# 503DC24.net
KiCad netlist of a schematic drawn in EAGLE
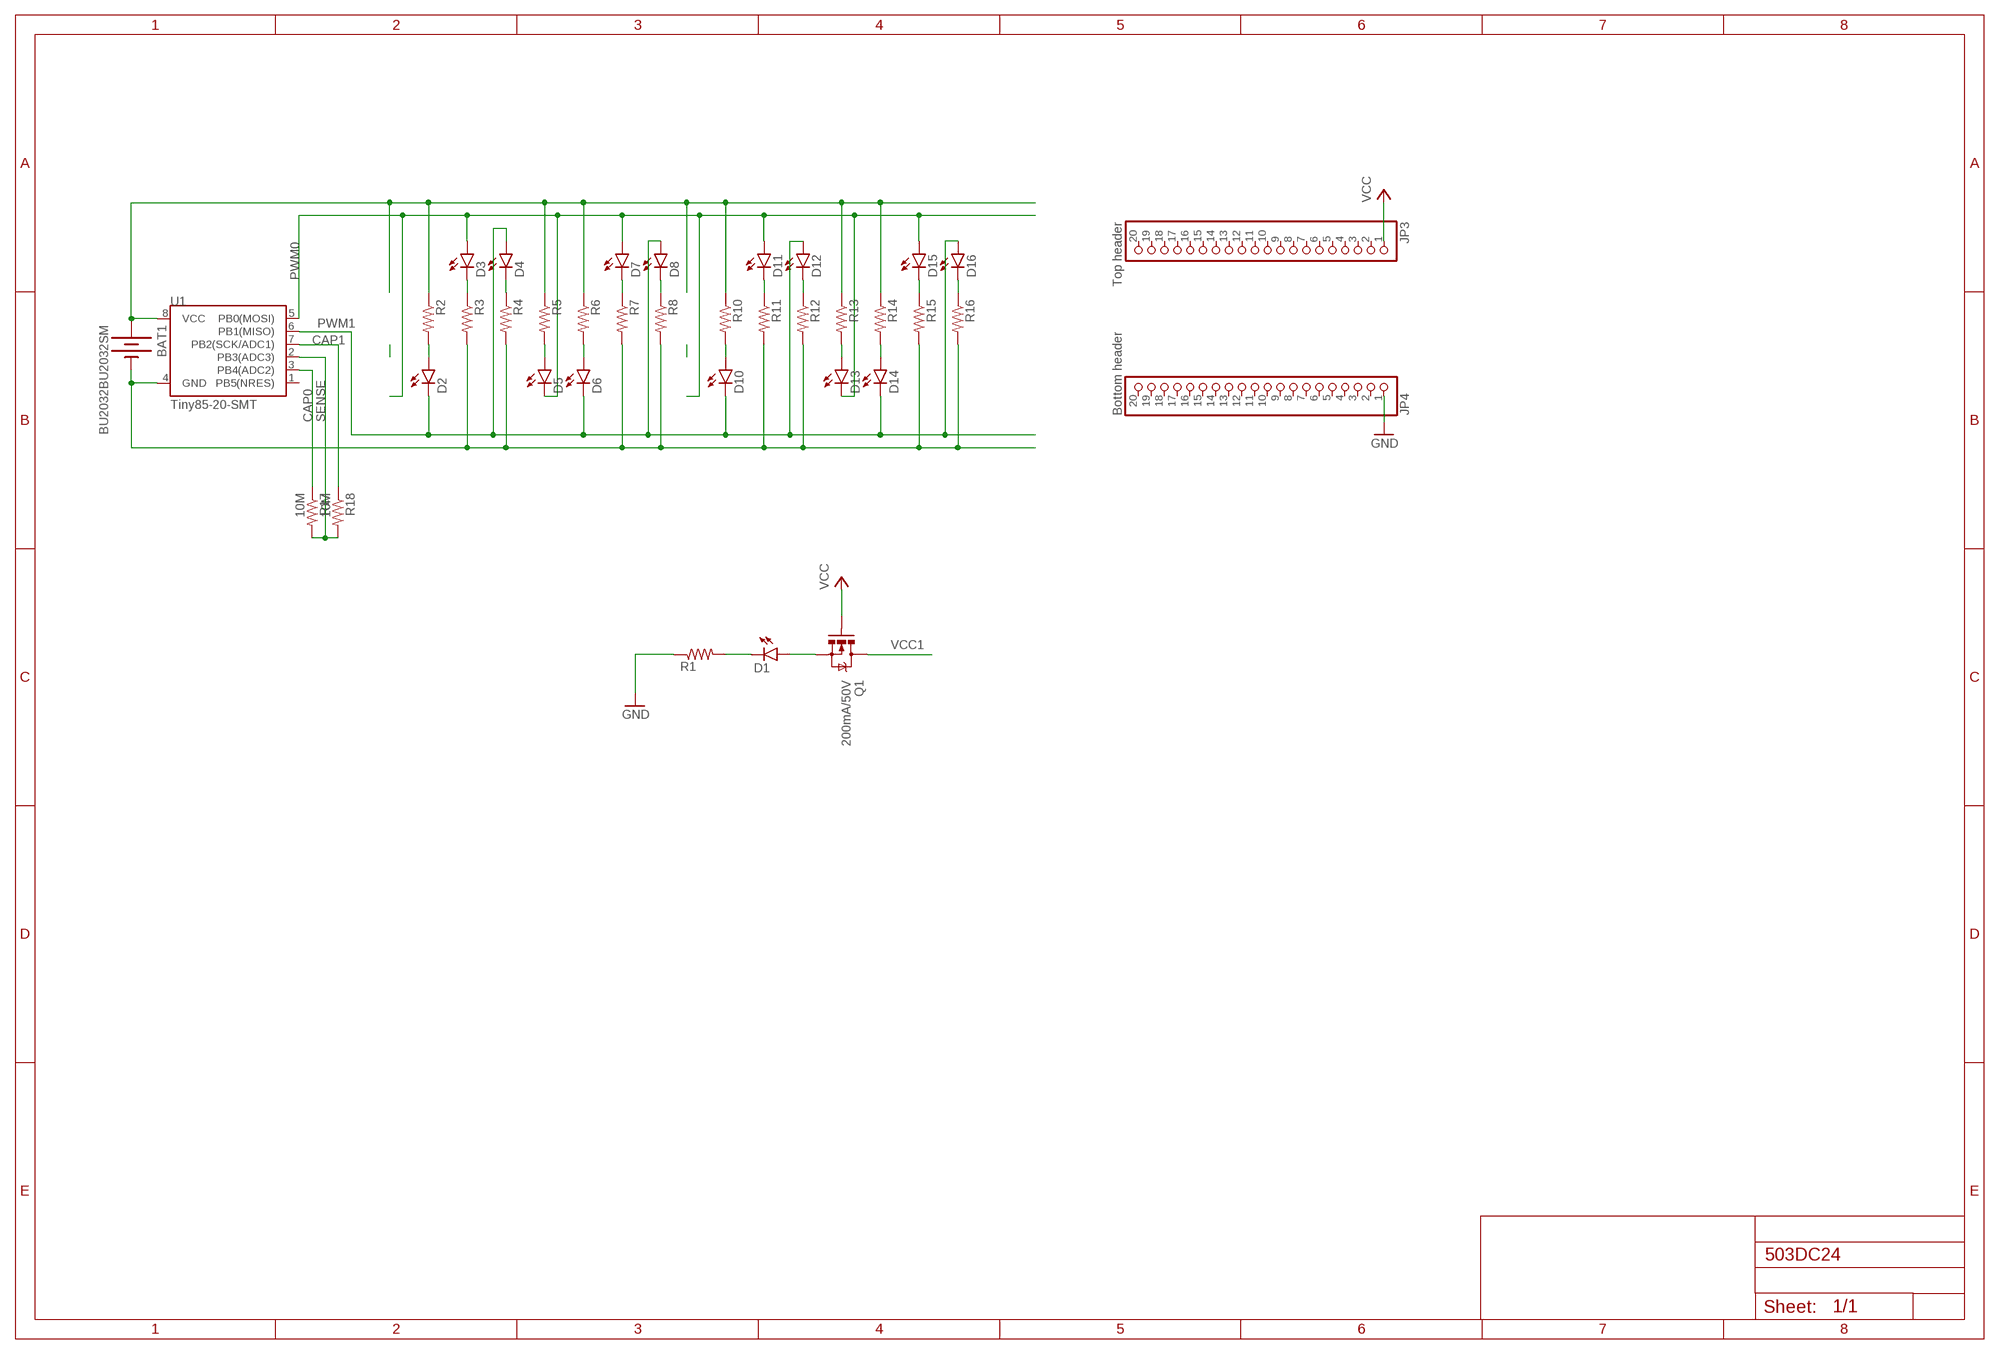
[diagram p0: schematic, sheet 1]

(export (version "E")
  (design (tool "Eeschema 10.0.6"))
  (components
    (comp (ref "BAT1")
      (value "BU2032BU2032SM")
      (footprint "eagle-import:BU2032SM")
      (libsource (lib "eagle-import") (part "BU2032BU2032SM"))
    )
    (comp (ref "D1")
      (value "LED1206-BOTTOM-SMALL_SILK")
      (footprint "eagle-import:LED-REV-MNT-SMALLSILK")
      (libsource (lib "eagle-import") (part "LED1206-BOTTOM-SMALL_SILK"))
    )
    (comp (ref "D2")
      (value "LED1206-BOTTOM-SMALL_SILK")
      (footprint "eagle-import:LED-REV-MNT-SMALLSILK")
      (libsource (lib "eagle-import") (part "LED1206-BOTTOM-SMALL_SILK"))
    )
    (comp (ref "D3")
      (value "LED1206-BOTTOM-SMALL_SILK")
      (footprint "eagle-import:LED-REV-MNT-SMALLSILK")
      (libsource (lib "eagle-import") (part "LED1206-BOTTOM-SMALL_SILK"))
    )
    (comp (ref "D4")
      (value "LED1206-BOTTOM-SMALL_SILK")
      (footprint "eagle-import:LED-REV-MNT-SMALLSILK")
      (libsource (lib "eagle-import") (part "LED1206-BOTTOM-SMALL_SILK"))
    )
    (comp (ref "D5")
      (value "LED1206-BOTTOM-SMALL_SILK")
      (footprint "eagle-import:LED-REV-MNT-SMALLSILK")
      (libsource (lib "eagle-import") (part "LED1206-BOTTOM-SMALL_SILK"))
    )
    (comp (ref "D6")
      (value "LED1206-BOTTOM-SMALL_SILK")
      (footprint "eagle-import:LED-REV-MNT-SMALLSILK")
      (libsource (lib "eagle-import") (part "LED1206-BOTTOM-SMALL_SILK"))
    )
    (comp (ref "D7")
      (value "LED1206-BOTTOM-SMALL_SILK")
      (footprint "eagle-import:LED-REV-MNT-SMALLSILK")
      (libsource (lib "eagle-import") (part "LED1206-BOTTOM-SMALL_SILK"))
    )
    (comp (ref "D8")
      (value "LED1206-BOTTOM-SMALL_SILK")
      (footprint "eagle-import:LED-REV-MNT-SMALLSILK")
      (libsource (lib "eagle-import") (part "LED1206-BOTTOM-SMALL_SILK"))
    )
    (comp (ref "D10")
      (value "LED1206-BOTTOM-SMALL_SILK")
      (footprint "eagle-import:LED-REV-MNT-SMALLSILK")
      (libsource (lib "eagle-import") (part "LED1206-BOTTOM-SMALL_SILK"))
    )
    (comp (ref "D11")
      (value "LED1206-BOTTOM-SMALL_SILK")
      (footprint "eagle-import:LED-REV-MNT-SMALLSILK")
      (libsource (lib "eagle-import") (part "LED1206-BOTTOM-SMALL_SILK"))
    )
    (comp (ref "D12")
      (value "LED1206-BOTTOM-SMALL_SILK")
      (footprint "eagle-import:LED-REV-MNT-SMALLSILK")
      (libsource (lib "eagle-import") (part "LED1206-BOTTOM-SMALL_SILK"))
    )
    (comp (ref "D13")
      (value "LED1206-BOTTOM-SMALL_SILK")
      (footprint "eagle-import:LED-REV-MNT-SMALLSILK")
      (libsource (lib "eagle-import") (part "LED1206-BOTTOM-SMALL_SILK"))
    )
    (comp (ref "D14")
      (value "LED1206-BOTTOM-SMALL_SILK")
      (footprint "eagle-import:LED-REV-MNT-SMALLSILK")
      (libsource (lib "eagle-import") (part "LED1206-BOTTOM-SMALL_SILK"))
    )
    (comp (ref "D15")
      (value "LED1206-BOTTOM-SMALL_SILK")
      (footprint "eagle-import:LED-REV-MNT-SMALLSILK")
      (libsource (lib "eagle-import") (part "LED1206-BOTTOM-SMALL_SILK"))
    )
    (comp (ref "D16")
      (value "LED1206-BOTTOM-SMALL_SILK")
      (footprint "eagle-import:LED-REV-MNT-SMALLSILK")
      (libsource (lib "eagle-import") (part "LED1206-BOTTOM-SMALL_SILK"))
    )
    (comp (ref "JP3")
      (value "Top header")
      (footprint "eagle-import:1X20")
      (libsource (lib "eagle-import") (part "PINHD-1X20"))
    )
    (comp (ref "JP4")
      (value "Bottom header")
      (footprint "eagle-import:1X20")
      (libsource (lib "eagle-import") (part "PINHD-1X20"))
    )
    (comp (ref "Q1")
      (value "200mA/50V")
      (footprint "eagle-import:SOT23-3")
      (libsource (lib "eagle-import") (part "MOSFET-NCHANNELBSS138"))
    )
    (comp (ref "R1")
      (value "RESISTOR1206")
      (footprint "eagle-import:1206")
      (libsource (lib "eagle-import") (part "RESISTOR1206"))
    )
    (comp (ref "R2")
      (value "RESISTOR1206")
      (footprint "eagle-import:1206")
      (libsource (lib "eagle-import") (part "RESISTOR1206"))
    )
    (comp (ref "R3")
      (value "RESISTOR1206")
      (footprint "eagle-import:1206")
      (libsource (lib "eagle-import") (part "RESISTOR1206"))
    )
    (comp (ref "R4")
      (value "RESISTOR1206")
      (footprint "eagle-import:1206")
      (libsource (lib "eagle-import") (part "RESISTOR1206"))
    )
    (comp (ref "R5")
      (value "RESISTOR1206")
      (footprint "eagle-import:1206")
      (libsource (lib "eagle-import") (part "RESISTOR1206"))
    )
    (comp (ref "R6")
      (value "RESISTOR1206")
      (footprint "eagle-import:1206")
      (libsource (lib "eagle-import") (part "RESISTOR1206"))
    )
    (comp (ref "R7")
      (value "RESISTOR1206")
      (footprint "eagle-import:1206")
      (libsource (lib "eagle-import") (part "RESISTOR1206"))
    )
    (comp (ref "R8")
      (value "RESISTOR1206")
      (footprint "eagle-import:1206")
      (libsource (lib "eagle-import") (part "RESISTOR1206"))
    )
    (comp (ref "R10")
      (value "RESISTOR1206")
      (footprint "eagle-import:1206")
      (libsource (lib "eagle-import") (part "RESISTOR1206"))
    )
    (comp (ref "R11")
      (value "RESISTOR1206")
      (footprint "eagle-import:1206")
      (libsource (lib "eagle-import") (part "RESISTOR1206"))
    )
    (comp (ref "R12")
      (value "RESISTOR1206")
      (footprint "eagle-import:1206")
      (libsource (lib "eagle-import") (part "RESISTOR1206"))
    )
    (comp (ref "R13")
      (value "RESISTOR1206")
      (footprint "eagle-import:1206")
      (libsource (lib "eagle-import") (part "RESISTOR1206"))
    )
    (comp (ref "R14")
      (value "RESISTOR1206")
      (footprint "eagle-import:1206")
      (libsource (lib "eagle-import") (part "RESISTOR1206"))
    )
    (comp (ref "R15")
      (value "RESISTOR1206")
      (footprint "eagle-import:1206")
      (libsource (lib "eagle-import") (part "RESISTOR1206"))
    )
    (comp (ref "R16")
      (value "RESISTOR1206")
      (footprint "eagle-import:1206")
      (libsource (lib "eagle-import") (part "RESISTOR1206"))
    )
    (comp (ref "R17")
      (value "10M")
      (footprint "eagle-import:0805")
      (libsource (lib "eagle-import") (part "RESISTOR0805-RES"))
    )
    (comp (ref "R18")
      (value "10M")
      (footprint "eagle-import:0805")
      (libsource (lib "eagle-import") (part "RESISTOR0805-RES"))
    )
    (comp (ref "U1")
      (value "Tiny85-20-SMT")
      (footprint "eagle-import:SO08-EIAJ")
      (libsource (lib "eagle-import") (part "ATTINY45TINY85-20-SMT"))
    )
  )
  (nets
    (net (code "1") (name "/CAP0") (class "Default")
      (node (ref "R17") (pin "1") (pinfunction "1_1") (pintype "passive"))
      (node (ref "U1") (pin "3") (pinfunction "PB4(ADC2)_3") (pintype "bidirectional"))
    )
    (net (code "2") (name "/CAP1") (class "Default")
      (node (ref "R18") (pin "1") (pinfunction "1_1") (pintype "passive"))
      (node (ref "U1") (pin "7") (pinfunction "PB2(SCK/ADC1)_7") (pintype "bidirectional"))
    )
    (net (code "3") (name "/PWM0") (class "Default")
      (node (ref "D11") (pin "A") (pinfunction "A_A") (pintype "passive"))
      (node (ref "D13") (pin "C") (pinfunction "C_C") (pintype "passive"))
      (node (ref "D15") (pin "A") (pinfunction "A_A") (pintype "passive"))
      (node (ref "D3") (pin "A") (pinfunction "A_A") (pintype "passive"))
      (node (ref "D5") (pin "C") (pinfunction "C_C") (pintype "passive"))
      (node (ref "D7") (pin "A") (pinfunction "A_A") (pintype "passive"))
      (node (ref "U1") (pin "5") (pinfunction "PB0(MOSI)_5") (pintype "bidirectional"))
    )
    (net (code "4") (name "/PWM1") (class "Default")
      (node (ref "D10") (pin "C") (pinfunction "C_C") (pintype "passive"))
      (node (ref "D12") (pin "A") (pinfunction "A_A") (pintype "passive"))
      (node (ref "D14") (pin "C") (pinfunction "C_C") (pintype "passive"))
      (node (ref "D16") (pin "A") (pinfunction "A_A") (pintype "passive"))
      (node (ref "D2") (pin "C") (pinfunction "C_C") (pintype "passive"))
      (node (ref "D4") (pin "A") (pinfunction "A_A") (pintype "passive"))
      (node (ref "D6") (pin "C") (pinfunction "C_C") (pintype "passive"))
      (node (ref "D8") (pin "A") (pinfunction "A_A") (pintype "passive"))
      (node (ref "U1") (pin "6") (pinfunction "PB1(MISO)_6") (pintype "bidirectional"))
    )
    (net (code "5") (name "/SENSE") (class "Default")
      (node (ref "R17") (pin "2") (pinfunction "2_2") (pintype "passive"))
      (node (ref "R18") (pin "2") (pinfunction "2_2") (pintype "passive"))
      (node (ref "U1") (pin "2") (pinfunction "PB3(ADC3)_2") (pintype "bidirectional"))
    )
    (net (code "6") (name "/VCC1") (class "Default")
      (node (ref "BAT1") (pin "P+") (pinfunction "+_P+") (pintype "power_in"))
      (node (ref "Q1") (pin "3") (pinfunction "D_3") (pintype "passive"))
      (node (ref "R10") (pin "1") (pinfunction "1_1") (pintype "passive"))
      (node (ref "R13") (pin "1") (pinfunction "1_1") (pintype "passive"))
      (node (ref "R14") (pin "1") (pinfunction "1_1") (pintype "passive"))
      (node (ref "R2") (pin "1") (pinfunction "1_1") (pintype "passive"))
      (node (ref "R5") (pin "1") (pinfunction "1_1") (pintype "passive"))
      (node (ref "R6") (pin "1") (pinfunction "1_1") (pintype "passive"))
      (node (ref "U1") (pin "8") (pinfunction "VCC_8") (pintype "bidirectional"))
    )
    (net (code "7") (name "GND") (class "Default")
      (node (ref "JP4") (pin "1") (pinfunction "1_1") (pintype "passive"))
      (node (ref "R1") (pin "1") (pinfunction "1_1") (pintype "passive"))
    )
    (net (code "8") (name "Net-(BAT1--)") (class "Default")
      (node (ref "BAT1") (pin "P-") (pinfunction "-_P-") (pintype "power_in"))
      (node (ref "R11") (pin "2") (pinfunction "2_2") (pintype "passive"))
      (node (ref "R12") (pin "2") (pinfunction "2_2") (pintype "passive"))
      (node (ref "R15") (pin "2") (pinfunction "2_2") (pintype "passive"))
      (node (ref "R16") (pin "2") (pinfunction "2_2") (pintype "passive"))
      (node (ref "R3") (pin "2") (pinfunction "2_2") (pintype "passive"))
      (node (ref "R4") (pin "2") (pinfunction "2_2") (pintype "passive"))
      (node (ref "R7") (pin "2") (pinfunction "2_2") (pintype "passive"))
      (node (ref "R8") (pin "2") (pinfunction "2_2") (pintype "passive"))
      (node (ref "U1") (pin "4") (pinfunction "GND_4") (pintype "bidirectional"))
    )
    (net (code "9") (name "Net-(D1-PadC)") (class "Default")
      (node (ref "D1") (pin "C") (pinfunction "C_C") (pintype "passive"))
      (node (ref "R1") (pin "2") (pinfunction "2_2") (pintype "passive"))
    )
    (net (code "10") (name "Net-(D2-PadA)") (class "Default")
      (node (ref "D2") (pin "A") (pinfunction "A_A") (pintype "passive"))
      (node (ref "R2") (pin "2") (pinfunction "2_2") (pintype "passive"))
    )
    (net (code "11") (name "Net-(D3-PadC)") (class "Default")
      (node (ref "D3") (pin "C") (pinfunction "C_C") (pintype "passive"))
      (node (ref "R3") (pin "1") (pinfunction "1_1") (pintype "passive"))
    )
    (net (code "12") (name "Net-(D4-PadC)") (class "Default")
      (node (ref "D4") (pin "C") (pinfunction "C_C") (pintype "passive"))
      (node (ref "R4") (pin "1") (pinfunction "1_1") (pintype "passive"))
    )
    (net (code "13") (name "Net-(D5-PadA)") (class "Default")
      (node (ref "D5") (pin "A") (pinfunction "A_A") (pintype "passive"))
      (node (ref "R5") (pin "2") (pinfunction "2_2") (pintype "passive"))
    )
    (net (code "14") (name "Net-(D6-PadA)") (class "Default")
      (node (ref "D6") (pin "A") (pinfunction "A_A") (pintype "passive"))
      (node (ref "R6") (pin "2") (pinfunction "2_2") (pintype "passive"))
    )
    (net (code "15") (name "Net-(D7-PadC)") (class "Default")
      (node (ref "D7") (pin "C") (pinfunction "C_C") (pintype "passive"))
      (node (ref "R7") (pin "1") (pinfunction "1_1") (pintype "passive"))
    )
    (net (code "16") (name "Net-(D8-PadC)") (class "Default")
      (node (ref "D8") (pin "C") (pinfunction "C_C") (pintype "passive"))
      (node (ref "R8") (pin "1") (pinfunction "1_1") (pintype "passive"))
    )
    (net (code "17") (name "Net-(D10-PadA)") (class "Default")
      (node (ref "D10") (pin "A") (pinfunction "A_A") (pintype "passive"))
      (node (ref "R10") (pin "2") (pinfunction "2_2") (pintype "passive"))
    )
    (net (code "18") (name "Net-(D11-PadC)") (class "Default")
      (node (ref "D11") (pin "C") (pinfunction "C_C") (pintype "passive"))
      (node (ref "R11") (pin "1") (pinfunction "1_1") (pintype "passive"))
    )
    (net (code "19") (name "Net-(D12-PadC)") (class "Default")
      (node (ref "D12") (pin "C") (pinfunction "C_C") (pintype "passive"))
      (node (ref "R12") (pin "1") (pinfunction "1_1") (pintype "passive"))
    )
    (net (code "20") (name "Net-(D13-PadA)") (class "Default")
      (node (ref "D13") (pin "A") (pinfunction "A_A") (pintype "passive"))
      (node (ref "R13") (pin "2") (pinfunction "2_2") (pintype "passive"))
    )
    (net (code "21") (name "Net-(D14-PadA)") (class "Default")
      (node (ref "D14") (pin "A") (pinfunction "A_A") (pintype "passive"))
      (node (ref "R14") (pin "2") (pinfunction "2_2") (pintype "passive"))
    )
    (net (code "22") (name "Net-(D15-PadC)") (class "Default")
      (node (ref "D15") (pin "C") (pinfunction "C_C") (pintype "passive"))
      (node (ref "R15") (pin "1") (pinfunction "1_1") (pintype "passive"))
    )
    (net (code "23") (name "Net-(D16-PadC)") (class "Default")
      (node (ref "D16") (pin "C") (pinfunction "C_C") (pintype "passive"))
      (node (ref "R16") (pin "1") (pinfunction "1_1") (pintype "passive"))
    )
    (net (code "24") (name "Net-(Q1-S)") (class "Default")
      (node (ref "D1") (pin "A") (pinfunction "A_A") (pintype "passive"))
      (node (ref "Q1") (pin "2") (pinfunction "S_2") (pintype "passive"))
    )
    (net (code "25") (name "VCC") (class "Default")
      (node (ref "JP3") (pin "1") (pinfunction "1_1") (pintype "passive"))
      (node (ref "Q1") (pin "1") (pinfunction "G_1") (pintype "passive"))
    )
    (net (code "26") (name "unconnected-(JP3-Pad2)") (class "Default")
      (node (ref "JP3") (pin "2") (pinfunction "2_2") (pintype "passive"))
    )
    (net (code "27") (name "unconnected-(JP3-Pad3)") (class "Default")
      (node (ref "JP3") (pin "3") (pinfunction "3_3") (pintype "passive"))
    )
    (net (code "28") (name "unconnected-(JP3-Pad4)") (class "Default")
      (node (ref "JP3") (pin "4") (pinfunction "4_4") (pintype "passive"))
    )
    (net (code "29") (name "unconnected-(JP3-Pad5)") (class "Default")
      (node (ref "JP3") (pin "5") (pinfunction "5_5") (pintype "passive"))
    )
    (net (code "30") (name "unconnected-(JP3-Pad6)") (class "Default")
      (node (ref "JP3") (pin "6") (pinfunction "6_6") (pintype "passive"))
    )
    (net (code "31") (name "unconnected-(JP3-Pad7)") (class "Default")
      (node (ref "JP3") (pin "7") (pinfunction "7_7") (pintype "passive"))
    )
    (net (code "32") (name "unconnected-(JP3-Pad8)") (class "Default")
      (node (ref "JP3") (pin "8") (pinfunction "8_8") (pintype "passive"))
    )
    (net (code "33") (name "unconnected-(JP3-Pad9)") (class "Default")
      (node (ref "JP3") (pin "9") (pinfunction "9_9") (pintype "passive"))
    )
    (net (code "34") (name "unconnected-(JP3-Pad10)") (class "Default")
      (node (ref "JP3") (pin "10") (pinfunction "10_10") (pintype "passive"))
    )
    (net (code "35") (name "unconnected-(JP3-Pad11)") (class "Default")
      (node (ref "JP3") (pin "11") (pinfunction "11_11") (pintype "passive"))
    )
    (net (code "36") (name "unconnected-(JP3-Pad12)") (class "Default")
      (node (ref "JP3") (pin "12") (pinfunction "12_12") (pintype "passive"))
    )
    (net (code "37") (name "unconnected-(JP3-Pad13)") (class "Default")
      (node (ref "JP3") (pin "13") (pinfunction "13_13") (pintype "passive"))
    )
    (net (code "38") (name "unconnected-(JP3-Pad14)") (class "Default")
      (node (ref "JP3") (pin "14") (pinfunction "14_14") (pintype "passive"))
    )
    (net (code "39") (name "unconnected-(JP3-Pad15)") (class "Default")
      (node (ref "JP3") (pin "15") (pinfunction "15_15") (pintype "passive"))
    )
    (net (code "40") (name "unconnected-(JP3-Pad16)") (class "Default")
      (node (ref "JP3") (pin "16") (pinfunction "16_16") (pintype "passive"))
    )
    (net (code "41") (name "unconnected-(JP3-Pad17)") (class "Default")
      (node (ref "JP3") (pin "17") (pinfunction "17_17") (pintype "passive"))
    )
    (net (code "42") (name "unconnected-(JP3-Pad18)") (class "Default")
      (node (ref "JP3") (pin "18") (pinfunction "18_18") (pintype "passive"))
    )
    (net (code "43") (name "unconnected-(JP3-Pad19)") (class "Default")
      (node (ref "JP3") (pin "19") (pinfunction "19_19") (pintype "passive"))
    )
    (net (code "44") (name "unconnected-(JP3-Pad20)") (class "Default")
      (node (ref "JP3") (pin "20") (pinfunction "20_20") (pintype "passive"))
    )
    (net (code "45") (name "unconnected-(JP4-Pad2)") (class "Default")
      (node (ref "JP4") (pin "2") (pinfunction "2_2") (pintype "passive"))
    )
    (net (code "46") (name "unconnected-(JP4-Pad3)") (class "Default")
      (node (ref "JP4") (pin "3") (pinfunction "3_3") (pintype "passive"))
    )
    (net (code "47") (name "unconnected-(JP4-Pad4)") (class "Default")
      (node (ref "JP4") (pin "4") (pinfunction "4_4") (pintype "passive"))
    )
    (net (code "48") (name "unconnected-(JP4-Pad5)") (class "Default")
      (node (ref "JP4") (pin "5") (pinfunction "5_5") (pintype "passive"))
    )
    (net (code "49") (name "unconnected-(JP4-Pad6)") (class "Default")
      (node (ref "JP4") (pin "6") (pinfunction "6_6") (pintype "passive"))
    )
    (net (code "50") (name "unconnected-(JP4-Pad7)") (class "Default")
      (node (ref "JP4") (pin "7") (pinfunction "7_7") (pintype "passive"))
    )
    (net (code "51") (name "unconnected-(JP4-Pad8)") (class "Default")
      (node (ref "JP4") (pin "8") (pinfunction "8_8") (pintype "passive"))
    )
    (net (code "52") (name "unconnected-(JP4-Pad9)") (class "Default")
      (node (ref "JP4") (pin "9") (pinfunction "9_9") (pintype "passive"))
    )
    (net (code "53") (name "unconnected-(JP4-Pad10)") (class "Default")
      (node (ref "JP4") (pin "10") (pinfunction "10_10") (pintype "passive"))
    )
    (net (code "54") (name "unconnected-(JP4-Pad11)") (class "Default")
      (node (ref "JP4") (pin "11") (pinfunction "11_11") (pintype "passive"))
    )
    (net (code "55") (name "unconnected-(JP4-Pad12)") (class "Default")
      (node (ref "JP4") (pin "12") (pinfunction "12_12") (pintype "passive"))
    )
    (net (code "56") (name "unconnected-(JP4-Pad13)") (class "Default")
      (node (ref "JP4") (pin "13") (pinfunction "13_13") (pintype "passive"))
    )
    (net (code "57") (name "unconnected-(JP4-Pad14)") (class "Default")
      (node (ref "JP4") (pin "14") (pinfunction "14_14") (pintype "passive"))
    )
    (net (code "58") (name "unconnected-(JP4-Pad15)") (class "Default")
      (node (ref "JP4") (pin "15") (pinfunction "15_15") (pintype "passive"))
    )
    (net (code "59") (name "unconnected-(JP4-Pad16)") (class "Default")
      (node (ref "JP4") (pin "16") (pinfunction "16_16") (pintype "passive"))
    )
    (net (code "60") (name "unconnected-(JP4-Pad17)") (class "Default")
      (node (ref "JP4") (pin "17") (pinfunction "17_17") (pintype "passive"))
    )
    (net (code "61") (name "unconnected-(JP4-Pad18)") (class "Default")
      (node (ref "JP4") (pin "18") (pinfunction "18_18") (pintype "passive"))
    )
    (net (code "62") (name "unconnected-(JP4-Pad19)") (class "Default")
      (node (ref "JP4") (pin "19") (pinfunction "19_19") (pintype "passive"))
    )
    (net (code "63") (name "unconnected-(JP4-Pad20)") (class "Default")
      (node (ref "JP4") (pin "20") (pinfunction "20_20") (pintype "passive"))
    )
    (net (code "64") (name "unconnected-(U1-PB5(NRES)-Pad1)") (class "Default")
      (node (ref "U1") (pin "1") (pinfunction "PB5(NRES)_1") (pintype "bidirectional"))
    )
  )
)
